# VSYNC_75px.net
KiCad netlist of a schematic drawn in EAGLE
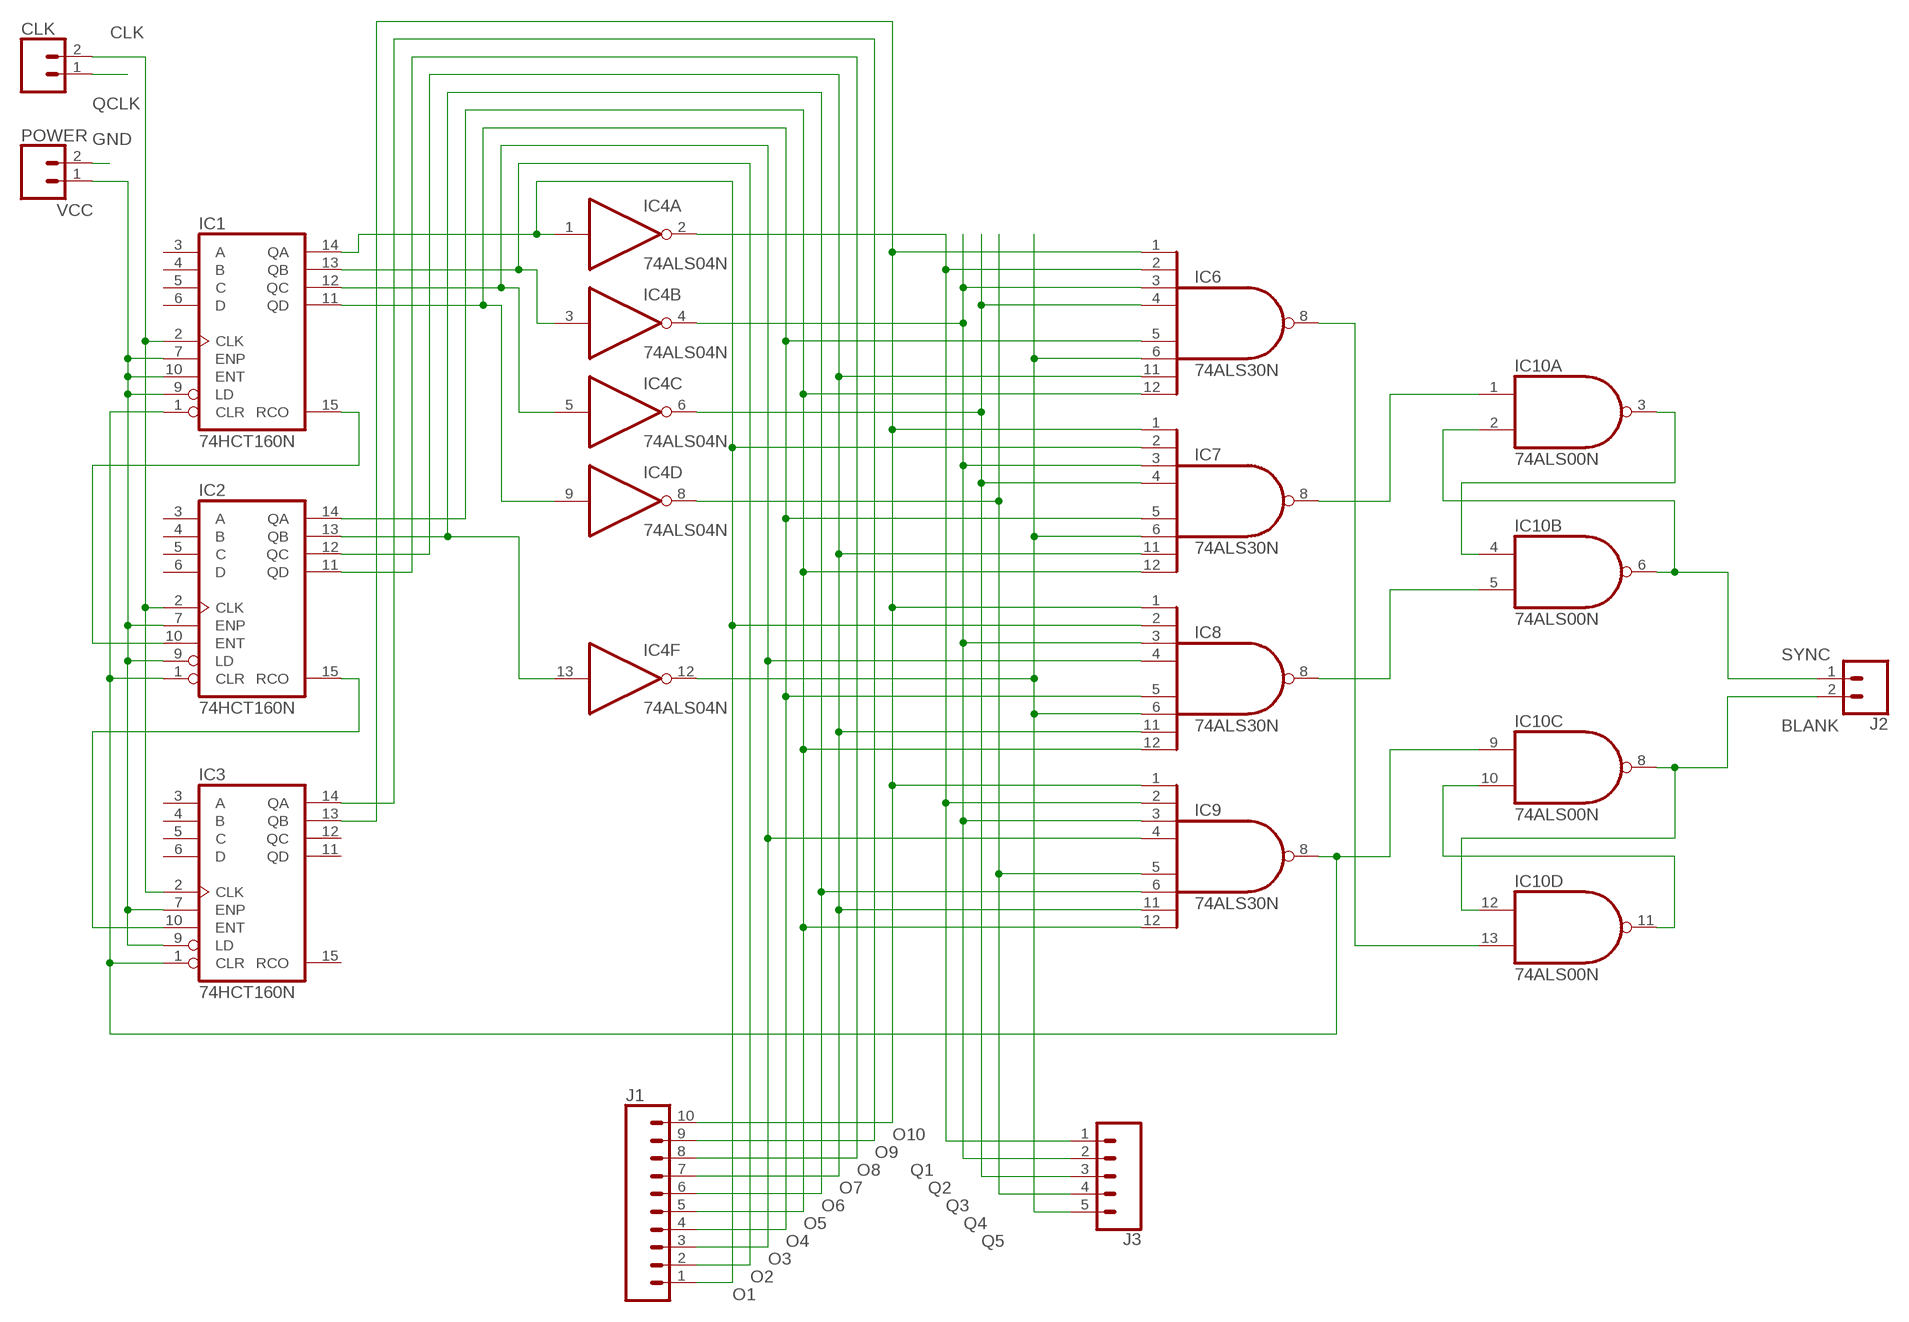
[diagram p0: schematic, sheet 1]

(export (version "E")
  (design (tool "Eeschema 10.0.6"))
  (components
    (comp (ref "CLK")
      (value "CONN_02POGO_PIN_HOLES_ONLY")
      (footprint "eagle-import:1X02_PP_HOLES_ONLY")
      (libsource (lib "eagle-import") (part "CONN_02POGO_PIN_HOLES_ONLY"))
    )
    (comp (ref "IC1")
      (value "74HCT160N")
      (footprint "eagle-import:DIL16")
      (libsource (lib "eagle-import") (part "74160NHCT"))
    )
    (comp (ref "IC2")
      (value "74HCT160N")
      (footprint "eagle-import:DIL16")
      (libsource (lib "eagle-import") (part "74160NHCT"))
    )
    (comp (ref "IC3")
      (value "74HCT160N")
      (footprint "eagle-import:DIL16")
      (libsource (lib "eagle-import") (part "74160NHCT"))
    )
    (comp (ref "IC4")
      (value "74ALS04N")
      (footprint "eagle-import:DIL14")
      (libsource (lib "eagle-import") (part "7404NALS"))
    )
    (comp (ref "IC6")
      (value "74ALS30N")
      (footprint "eagle-import:DIL14")
      (libsource (lib "eagle-import") (part "7430NALS"))
    )
    (comp (ref "IC7")
      (value "74ALS30N")
      (footprint "eagle-import:DIL14")
      (libsource (lib "eagle-import") (part "7430NALS"))
    )
    (comp (ref "IC8")
      (value "74ALS30N")
      (footprint "eagle-import:DIL14")
      (libsource (lib "eagle-import") (part "7430NALS"))
    )
    (comp (ref "IC9")
      (value "74ALS30N")
      (footprint "eagle-import:DIL14")
      (libsource (lib "eagle-import") (part "7430NALS"))
    )
    (comp (ref "IC10")
      (value "74ALS00N")
      (footprint "eagle-import:DIL14")
      (libsource (lib "eagle-import") (part "7400NALS"))
    )
    (comp (ref "J1")
      (value "CONN_10\"")
      (footprint "eagle-import:1X10")
      (libsource (lib "eagle-import") (part "CONN_10{dblquote}"))
    )
    (comp (ref "J2")
      (value "CONN_02POGO_PIN_HOLES_ONLY")
      (footprint "eagle-import:1X02_PP_HOLES_ONLY")
      (libsource (lib "eagle-import") (part "CONN_02POGO_PIN_HOLES_ONLY"))
    )
    (comp (ref "J3")
      (value "CONN_05")
      (footprint "eagle-import:1X05")
      (libsource (lib "eagle-import") (part "CONN_05"))
    )
    (comp (ref "POWER")
      (value "CONN_02POGO_PIN_HOLES_ONLY")
      (footprint "eagle-import:1X02_PP_HOLES_ONLY")
      (libsource (lib "eagle-import") (part "CONN_02POGO_PIN_HOLES_ONLY"))
    )
  )
  (nets
    (net (code "1") (name "/BLANK") (class "Default")
      (node (ref "IC10") (pin "12") (pinfunction "I0_12") (pintype "input"))
      (node (ref "IC10") (pin "8") (pinfunction "O_8") (pintype "output"))
      (node (ref "J2") (pin "2") (pinfunction "2_2") (pintype "passive"))
    )
    (net (code "2") (name "/CLK") (class "Default")
      (node (ref "CLK") (pin "2") (pinfunction "2_2") (pintype "passive"))
      (node (ref "IC1") (pin "2") (pinfunction "CLK_2") (pintype "input"))
      (node (ref "IC2") (pin "2") (pinfunction "CLK_2") (pintype "input"))
      (node (ref "IC3") (pin "2") (pinfunction "CLK_2") (pintype "input"))
    )
    (net (code "3") (name "/GND") (class "Default")
      (node (ref "POWER") (pin "2") (pinfunction "2_2") (pintype "passive"))
    )
    (net (code "4") (name "/O1") (class "Default")
      (node (ref "IC1") (pin "14") (pinfunction "QA_14") (pintype "output"))
      (node (ref "IC4") (pin "1") (pinfunction "I_1") (pintype "input"))
      (node (ref "IC7") (pin "2") (pinfunction "I1_2") (pintype "input"))
      (node (ref "IC8") (pin "2") (pinfunction "I1_2") (pintype "input"))
      (node (ref "J1") (pin "1") (pinfunction "1_1") (pintype "passive"))
    )
    (net (code "5") (name "/O2") (class "Default")
      (node (ref "IC1") (pin "13") (pinfunction "QB_13") (pintype "output"))
      (node (ref "IC4") (pin "3") (pinfunction "I_3") (pintype "input"))
      (node (ref "J1") (pin "2") (pinfunction "2_2") (pintype "passive"))
    )
    (net (code "6") (name "/O3") (class "Default")
      (node (ref "IC1") (pin "12") (pinfunction "QC_12") (pintype "output"))
      (node (ref "IC4") (pin "5") (pinfunction "I_5") (pintype "input"))
      (node (ref "IC8") (pin "4") (pinfunction "I3_4") (pintype "input"))
      (node (ref "IC9") (pin "4") (pinfunction "I3_4") (pintype "input"))
      (node (ref "J1") (pin "3") (pinfunction "3_3") (pintype "passive"))
    )
    (net (code "7") (name "/O4") (class "Default")
      (node (ref "IC1") (pin "11") (pinfunction "QD_11") (pintype "output"))
      (node (ref "IC4") (pin "9") (pinfunction "I_9") (pintype "input"))
      (node (ref "IC6") (pin "5") (pinfunction "I4_5") (pintype "input"))
      (node (ref "IC7") (pin "5") (pinfunction "I4_5") (pintype "input"))
      (node (ref "IC8") (pin "5") (pinfunction "I4_5") (pintype "input"))
      (node (ref "J1") (pin "4") (pinfunction "4_4") (pintype "passive"))
    )
    (net (code "8") (name "/O5") (class "Default")
      (node (ref "IC2") (pin "14") (pinfunction "QA_14") (pintype "output"))
      (node (ref "IC6") (pin "12") (pinfunction "I7_12") (pintype "input"))
      (node (ref "IC7") (pin "12") (pinfunction "I7_12") (pintype "input"))
      (node (ref "IC8") (pin "12") (pinfunction "I7_12") (pintype "input"))
      (node (ref "IC9") (pin "12") (pinfunction "I7_12") (pintype "input"))
      (node (ref "J1") (pin "5") (pinfunction "5_5") (pintype "passive"))
    )
    (net (code "9") (name "/O6") (class "Default")
      (node (ref "IC2") (pin "13") (pinfunction "QB_13") (pintype "output"))
      (node (ref "IC4") (pin "13") (pinfunction "I_13") (pintype "input"))
      (node (ref "IC9") (pin "6") (pinfunction "I5_6") (pintype "input"))
      (node (ref "J1") (pin "6") (pinfunction "6_6") (pintype "passive"))
    )
    (net (code "10") (name "/O7") (class "Default")
      (node (ref "IC2") (pin "12") (pinfunction "QC_12") (pintype "output"))
      (node (ref "IC6") (pin "11") (pinfunction "I6_11") (pintype "input"))
      (node (ref "IC7") (pin "11") (pinfunction "I6_11") (pintype "input"))
      (node (ref "IC8") (pin "11") (pinfunction "I6_11") (pintype "input"))
      (node (ref "IC9") (pin "11") (pinfunction "I6_11") (pintype "input"))
      (node (ref "J1") (pin "7") (pinfunction "7_7") (pintype "passive"))
    )
    (net (code "11") (name "/O8") (class "Default")
      (node (ref "IC2") (pin "11") (pinfunction "QD_11") (pintype "output"))
      (node (ref "J1") (pin "8") (pinfunction "8_8") (pintype "passive"))
    )
    (net (code "12") (name "/O9") (class "Default")
      (node (ref "IC3") (pin "14") (pinfunction "QA_14") (pintype "output"))
      (node (ref "J1") (pin "9") (pinfunction "9_9") (pintype "passive"))
    )
    (net (code "13") (name "/O10") (class "Default")
      (node (ref "IC3") (pin "13") (pinfunction "QB_13") (pintype "output"))
      (node (ref "IC6") (pin "1") (pinfunction "I0_1") (pintype "input"))
      (node (ref "IC7") (pin "1") (pinfunction "I0_1") (pintype "input"))
      (node (ref "IC8") (pin "1") (pinfunction "I0_1") (pintype "input"))
      (node (ref "IC9") (pin "1") (pinfunction "I0_1") (pintype "input"))
      (node (ref "J1") (pin "10") (pinfunction "10_10") (pintype "passive"))
    )
    (net (code "14") (name "/Q1") (class "Default")
      (node (ref "IC4") (pin "2") (pinfunction "O_2") (pintype "output"))
      (node (ref "IC6") (pin "2") (pinfunction "I1_2") (pintype "input"))
      (node (ref "IC9") (pin "2") (pinfunction "I1_2") (pintype "input"))
      (node (ref "J3") (pin "1") (pinfunction "1_1") (pintype "passive"))
    )
    (net (code "15") (name "/Q2") (class "Default")
      (node (ref "IC4") (pin "4") (pinfunction "O_4") (pintype "output"))
      (node (ref "IC6") (pin "3") (pinfunction "I2_3") (pintype "input"))
      (node (ref "IC7") (pin "3") (pinfunction "I2_3") (pintype "input"))
      (node (ref "IC8") (pin "3") (pinfunction "I2_3") (pintype "input"))
      (node (ref "IC9") (pin "3") (pinfunction "I2_3") (pintype "input"))
      (node (ref "J3") (pin "2") (pinfunction "2_2") (pintype "passive"))
    )
    (net (code "16") (name "/Q3") (class "Default")
      (node (ref "IC4") (pin "6") (pinfunction "O_6") (pintype "output"))
      (node (ref "IC6") (pin "4") (pinfunction "I3_4") (pintype "input"))
      (node (ref "IC7") (pin "4") (pinfunction "I3_4") (pintype "input"))
      (node (ref "J3") (pin "3") (pinfunction "3_3") (pintype "passive"))
    )
    (net (code "17") (name "/Q4") (class "Default")
      (node (ref "IC4") (pin "8") (pinfunction "O_8") (pintype "output"))
      (node (ref "IC9") (pin "5") (pinfunction "I4_5") (pintype "input"))
      (node (ref "J3") (pin "4") (pinfunction "4_4") (pintype "passive"))
    )
    (net (code "18") (name "/Q5") (class "Default")
      (node (ref "IC4") (pin "12") (pinfunction "O_12") (pintype "output"))
      (node (ref "IC6") (pin "6") (pinfunction "I5_6") (pintype "input"))
      (node (ref "IC7") (pin "6") (pinfunction "I5_6") (pintype "input"))
      (node (ref "IC8") (pin "6") (pinfunction "I5_6") (pintype "input"))
      (node (ref "J3") (pin "5") (pinfunction "5_5") (pintype "passive"))
    )
    (net (code "19") (name "/QCLK") (class "Default")
      (node (ref "CLK") (pin "1") (pinfunction "1_1") (pintype "passive"))
    )
    (net (code "20") (name "/SYNC") (class "Default")
      (node (ref "IC10") (pin "2") (pinfunction "I1_2") (pintype "input"))
      (node (ref "IC10") (pin "6") (pinfunction "O_6") (pintype "output"))
      (node (ref "J2") (pin "1") (pinfunction "1_1") (pintype "passive"))
    )
    (net (code "21") (name "/VCC") (class "Default")
      (node (ref "IC1") (pin "10") (pinfunction "ENT_10") (pintype "input"))
      (node (ref "IC1") (pin "7") (pinfunction "ENP_7") (pintype "input"))
      (node (ref "IC1") (pin "9") (pinfunction "LD_9") (pintype "input"))
      (node (ref "IC2") (pin "7") (pinfunction "ENP_7") (pintype "input"))
      (node (ref "IC2") (pin "9") (pinfunction "LD_9") (pintype "input"))
      (node (ref "IC3") (pin "7") (pinfunction "ENP_7") (pintype "input"))
      (node (ref "IC3") (pin "9") (pinfunction "LD_9") (pintype "input"))
      (node (ref "POWER") (pin "1") (pinfunction "1_1") (pintype "passive"))
    )
    (net (code "22") (name "Net-(IC1A-RCO)") (class "Default")
      (node (ref "IC1") (pin "15") (pinfunction "RCO_15") (pintype "output"))
      (node (ref "IC2") (pin "10") (pinfunction "ENT_10") (pintype "input"))
    )
    (net (code "23") (name "Net-(IC2A-RCO)") (class "Default")
      (node (ref "IC2") (pin "15") (pinfunction "RCO_15") (pintype "output"))
      (node (ref "IC3") (pin "10") (pinfunction "ENT_10") (pintype "input"))
    )
    (net (code "24") (name "Net-(IC10A-I0)") (class "Default")
      (node (ref "IC10") (pin "1") (pinfunction "I0_1") (pintype "input"))
      (node (ref "IC7") (pin "8") (pinfunction "O_8") (pintype "output"))
    )
    (net (code "25") (name "Net-(IC10A-O)") (class "Default")
      (node (ref "IC10") (pin "3") (pinfunction "O_3") (pintype "output"))
      (node (ref "IC10") (pin "4") (pinfunction "I0_4") (pintype "input"))
    )
    (net (code "26") (name "Net-(IC10B-I1)") (class "Default")
      (node (ref "IC10") (pin "5") (pinfunction "I1_5") (pintype "input"))
      (node (ref "IC8") (pin "8") (pinfunction "O_8") (pintype "output"))
    )
    (net (code "27") (name "Net-(IC10C-I0)") (class "Default")
      (node (ref "IC1") (pin "1") (pinfunction "CLR_1") (pintype "input"))
      (node (ref "IC10") (pin "9") (pinfunction "I0_9") (pintype "input"))
      (node (ref "IC2") (pin "1") (pinfunction "CLR_1") (pintype "input"))
      (node (ref "IC3") (pin "1") (pinfunction "CLR_1") (pintype "input"))
      (node (ref "IC9") (pin "8") (pinfunction "O_8") (pintype "output"))
    )
    (net (code "28") (name "Net-(IC10C-I1)") (class "Default")
      (node (ref "IC10") (pin "10") (pinfunction "I1_10") (pintype "input"))
      (node (ref "IC10") (pin "11") (pinfunction "O_11") (pintype "output"))
    )
    (net (code "29") (name "Net-(IC10D-I1)") (class "Default")
      (node (ref "IC10") (pin "13") (pinfunction "I1_13") (pintype "input"))
      (node (ref "IC6") (pin "8") (pinfunction "O_8") (pintype "output"))
    )
    (net (code "30") (name "unconnected-(IC1A-A-Pad3)") (class "Default")
      (node (ref "IC1") (pin "3") (pinfunction "A_3") (pintype "input"))
    )
    (net (code "31") (name "unconnected-(IC1A-B-Pad4)") (class "Default")
      (node (ref "IC1") (pin "4") (pinfunction "B_4") (pintype "input"))
    )
    (net (code "32") (name "unconnected-(IC1A-C-Pad5)") (class "Default")
      (node (ref "IC1") (pin "5") (pinfunction "C_5") (pintype "input"))
    )
    (net (code "33") (name "unconnected-(IC1A-D-Pad6)") (class "Default")
      (node (ref "IC1") (pin "6") (pinfunction "D_6") (pintype "input"))
    )
    (net (code "34") (name "unconnected-(IC2A-A-Pad3)") (class "Default")
      (node (ref "IC2") (pin "3") (pinfunction "A_3") (pintype "input"))
    )
    (net (code "35") (name "unconnected-(IC2A-B-Pad4)") (class "Default")
      (node (ref "IC2") (pin "4") (pinfunction "B_4") (pintype "input"))
    )
    (net (code "36") (name "unconnected-(IC2A-C-Pad5)") (class "Default")
      (node (ref "IC2") (pin "5") (pinfunction "C_5") (pintype "input"))
    )
    (net (code "37") (name "unconnected-(IC2A-D-Pad6)") (class "Default")
      (node (ref "IC2") (pin "6") (pinfunction "D_6") (pintype "input"))
    )
    (net (code "38") (name "unconnected-(IC3A-A-Pad3)") (class "Default")
      (node (ref "IC3") (pin "3") (pinfunction "A_3") (pintype "input"))
    )
    (net (code "39") (name "unconnected-(IC3A-B-Pad4)") (class "Default")
      (node (ref "IC3") (pin "4") (pinfunction "B_4") (pintype "input"))
    )
    (net (code "40") (name "unconnected-(IC3A-C-Pad5)") (class "Default")
      (node (ref "IC3") (pin "5") (pinfunction "C_5") (pintype "input"))
    )
    (net (code "41") (name "unconnected-(IC3A-D-Pad6)") (class "Default")
      (node (ref "IC3") (pin "6") (pinfunction "D_6") (pintype "input"))
    )
    (net (code "42") (name "unconnected-(IC3A-QC-Pad12)") (class "Default")
      (node (ref "IC3") (pin "12") (pinfunction "QC_12") (pintype "output"))
    )
    (net (code "43") (name "unconnected-(IC3A-QD-Pad11)") (class "Default")
      (node (ref "IC3") (pin "11") (pinfunction "QD_11") (pintype "output"))
    )
    (net (code "44") (name "unconnected-(IC3A-RCO-Pad15)") (class "Default")
      (node (ref "IC3") (pin "15") (pinfunction "RCO_15") (pintype "output"))
    )
  )
)
